# wsbd_wide.net
KiCad netlist of a schematic drawn in EAGLE
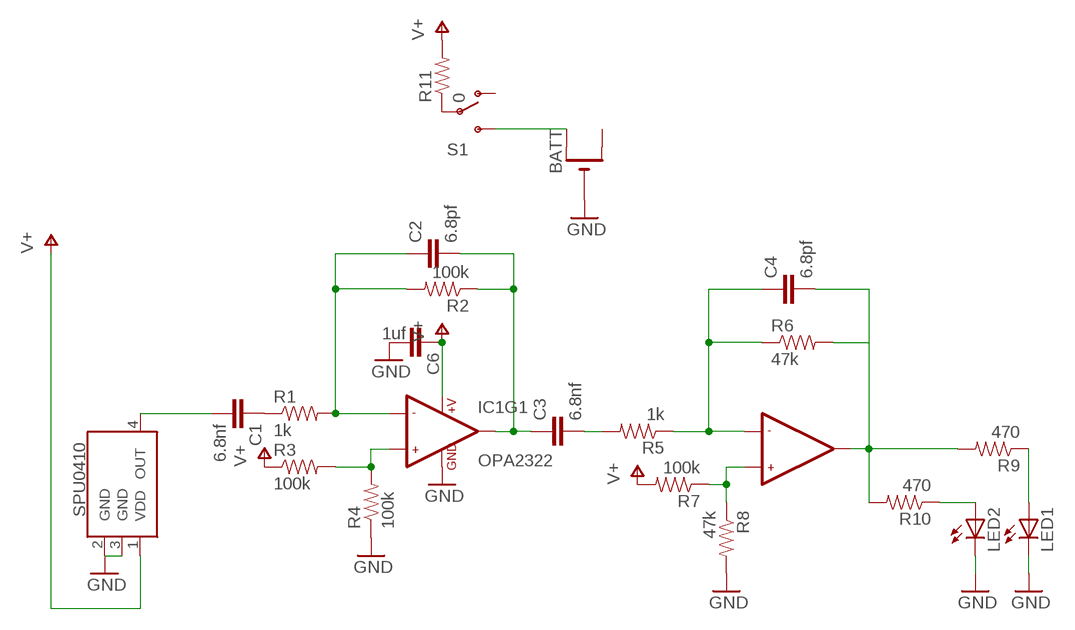
[diagram p0: schematic, sheet 1]

(export (version "E")
  (design (tool "Eeschema 10.0.6"))
  (components
    (comp (ref "BATT")
      (value "CR2032MPD1")
      (footprint "eagle-import:CR2032-THRU")
      (libsource (lib "eagle-import") (part "CR2032MPD1"))
    )
    (comp (ref "C1")
      (value "6.8nf")
      (footprint "eagle-import:0805")
      (libsource (lib "eagle-import") (part "CAP0805"))
    )
    (comp (ref "C2")
      (value "6.8pf")
      (footprint "eagle-import:0805")
      (libsource (lib "eagle-import") (part "CAP0805"))
    )
    (comp (ref "C3")
      (value "6.8nf")
      (footprint "eagle-import:0805")
      (libsource (lib "eagle-import") (part "CAP0805"))
    )
    (comp (ref "C4")
      (value "6.8pf")
      (footprint "eagle-import:0805")
      (libsource (lib "eagle-import") (part "CAP0805"))
    )
    (comp (ref "C6")
      (value "1uf")
      (footprint "eagle-import:0805")
      (libsource (lib "eagle-import") (part "CAP0805"))
    )
    (comp (ref "IC1")
      (value "OPA2322")
      (footprint "eagle-import:SO08")
      (libsource (lib "eagle-import") (part "LMV358SOIC"))
    )
    (comp (ref "LED1")
      (value "LEDCHIP-LED0805")
      (footprint "eagle-import:CHIP-LED0805")
      (libsource (lib "eagle-import") (part "LEDCHIP-LED0805"))
    )
    (comp (ref "LED2")
      (value "LEDCHIP-LED0805")
      (footprint "eagle-import:CHIP-LED0805")
      (libsource (lib "eagle-import") (part "LEDCHIP-LED0805"))
    )
    (comp (ref "R1")
      (value "1k")
      (footprint "eagle-import:0805")
      (libsource (lib "eagle-import") (part "RESISTOR0805-RES"))
    )
    (comp (ref "R2")
      (value "100k")
      (footprint "eagle-import:0805")
      (libsource (lib "eagle-import") (part "RESISTOR0805-RES"))
    )
    (comp (ref "R3")
      (value "100k")
      (footprint "eagle-import:0805")
      (libsource (lib "eagle-import") (part "RESISTOR0805-RES"))
    )
    (comp (ref "R4")
      (value "100k")
      (footprint "eagle-import:0805")
      (libsource (lib "eagle-import") (part "RESISTOR0805-RES"))
    )
    (comp (ref "R5")
      (value "1k")
      (footprint "eagle-import:0805")
      (libsource (lib "eagle-import") (part "RESISTOR0805-RES"))
    )
    (comp (ref "R6")
      (value "47k")
      (footprint "eagle-import:0805")
      (libsource (lib "eagle-import") (part "RESISTOR0805-RES"))
    )
    (comp (ref "R7")
      (value "100k")
      (footprint "eagle-import:0805")
      (libsource (lib "eagle-import") (part "RESISTOR0805-RES"))
    )
    (comp (ref "R8")
      (value "47k")
      (footprint "eagle-import:0805")
      (libsource (lib "eagle-import") (part "RESISTOR0805-RES"))
    )
    (comp (ref "R9")
      (value "470")
      (footprint "eagle-import:0805")
      (libsource (lib "eagle-import") (part "RESISTOR0805-RES"))
    )
    (comp (ref "R10")
      (value "470")
      (footprint "eagle-import:0805")
      (libsource (lib "eagle-import") (part "RESISTOR0805-RES"))
    )
    (comp (ref "R11")
      (value "0")
      (footprint "eagle-import:0805")
      (libsource (lib "eagle-import") (part "RESISTOR0805-RES"))
    )
    (comp (ref "S1")
      (value "SWITCH-SPDT-SMD-A")
      (footprint "eagle-import:SWITCH-SPST-SMD-A")
      (libsource (lib "eagle-import") (part "SWITCH-SPDT-SMD-A"))
    )
    (comp (ref "U$1")
      (value "SPU0410")
      (footprint "eagle-import:SPSERIES1")
      (libsource (lib "eagle-import") (part "SPU0410"))
    )
  )
  (nets
    (net (code "1") (name "GND") (class "Default")
      (node (ref "BATT") (pin "GND") (pinfunction "-_GND") (pintype "passive"))
      (node (ref "C6") (pin "2") (pinfunction "2_2") (pintype "passive"))
      (node (ref "IC1") (pin "4") (pinfunction "GND_4") (pintype "power_in"))
      (node (ref "LED1") (pin "C") (pinfunction "C_C") (pintype "passive"))
      (node (ref "LED2") (pin "C") (pinfunction "C_C") (pintype "passive"))
      (node (ref "R4") (pin "1") (pinfunction "1_1") (pintype "passive"))
      (node (ref "R8") (pin "2") (pinfunction "2_2") (pintype "passive"))
      (node (ref "U$1") (pin "2") (pinfunction "GND_2") (pintype "bidirectional"))
      (node (ref "U$1") (pin "3") (pinfunction "GND_3") (pintype "bidirectional"))
    )
    (net (code "2") (name "Net-(BATT-+)") (class "Default")
      (node (ref "BATT") (pin "+1") (pinfunction "+_+1") (pintype "passive"))
      (node (ref "S1") (pin "3") (pinfunction "S_3") (pintype "passive"))
    )
    (net (code "3") (name "Net-(C1-Pad1)") (class "Default")
      (node (ref "C1") (pin "1") (pinfunction "1_1") (pintype "passive"))
      (node (ref "R1") (pin "1") (pinfunction "1_1") (pintype "passive"))
    )
    (net (code "4") (name "Net-(C3-Pad2)") (class "Default")
      (node (ref "C3") (pin "2") (pinfunction "2_2") (pintype "passive"))
      (node (ref "R5") (pin "2") (pinfunction "2_2") (pintype "passive"))
    )
    (net (code "5") (name "Net-(IC1A-+IN1)") (class "Default")
      (node (ref "IC1") (pin "3") (pinfunction "+IN1_3") (pintype "input"))
      (node (ref "R3") (pin "2") (pinfunction "2_2") (pintype "passive"))
      (node (ref "R4") (pin "2") (pinfunction "2_2") (pintype "passive"))
    )
    (net (code "6") (name "Net-(IC1A--IN1)") (class "Default")
      (node (ref "C2") (pin "1") (pinfunction "1_1") (pintype "passive"))
      (node (ref "IC1") (pin "2") (pinfunction "-IN1_2") (pintype "input"))
      (node (ref "R1") (pin "2") (pinfunction "2_2") (pintype "passive"))
      (node (ref "R2") (pin "2") (pinfunction "2_2") (pintype "passive"))
    )
    (net (code "7") (name "Net-(IC1A-OUT1)") (class "Default")
      (node (ref "C2") (pin "2") (pinfunction "2_2") (pintype "passive"))
      (node (ref "C3") (pin "1") (pinfunction "1_1") (pintype "passive"))
      (node (ref "IC1") (pin "1") (pinfunction "OUT1_1") (pintype "output"))
      (node (ref "R2") (pin "1") (pinfunction "1_1") (pintype "passive"))
    )
    (net (code "8") (name "Net-(IC1B-+IN2)") (class "Default")
      (node (ref "IC1") (pin "5") (pinfunction "+IN2_5") (pintype "input"))
      (node (ref "R7") (pin "1") (pinfunction "1_1") (pintype "passive"))
      (node (ref "R8") (pin "1") (pinfunction "1_1") (pintype "passive"))
    )
    (net (code "9") (name "Net-(IC1B--IN2)") (class "Default")
      (node (ref "C4") (pin "1") (pinfunction "1_1") (pintype "passive"))
      (node (ref "IC1") (pin "6") (pinfunction "-IN2_6") (pintype "input"))
      (node (ref "R5") (pin "1") (pinfunction "1_1") (pintype "passive"))
      (node (ref "R6") (pin "1") (pinfunction "1_1") (pintype "passive"))
    )
    (net (code "10") (name "Net-(IC1B-OUT2)") (class "Default")
      (node (ref "C4") (pin "2") (pinfunction "2_2") (pintype "passive"))
      (node (ref "IC1") (pin "7") (pinfunction "OUT2_7") (pintype "output"))
      (node (ref "R10") (pin "2") (pinfunction "2_2") (pintype "passive"))
      (node (ref "R6") (pin "2") (pinfunction "2_2") (pintype "passive"))
      (node (ref "R9") (pin "2") (pinfunction "2_2") (pintype "passive"))
    )
    (net (code "11") (name "Net-(LED1-PadA)") (class "Default")
      (node (ref "LED1") (pin "A") (pinfunction "A_A") (pintype "passive"))
      (node (ref "R9") (pin "1") (pinfunction "1_1") (pintype "passive"))
    )
    (net (code "12") (name "Net-(LED2-PadA)") (class "Default")
      (node (ref "LED2") (pin "A") (pinfunction "A_A") (pintype "passive"))
      (node (ref "R10") (pin "1") (pinfunction "1_1") (pintype "passive"))
    )
    (net (code "13") (name "Net-(S1-P)") (class "Default")
      (node (ref "R11") (pin "1") (pinfunction "1_1") (pintype "passive"))
      (node (ref "S1") (pin "2") (pinfunction "P_2") (pintype "passive"))
    )
    (net (code "14") (name "Net-(U$1-OUT)") (class "Default")
      (node (ref "C1") (pin "2") (pinfunction "2_2") (pintype "passive"))
      (node (ref "U$1") (pin "4") (pinfunction "OUT_4") (pintype "bidirectional"))
    )
    (net (code "15") (name "V+") (class "Default")
      (node (ref "C6") (pin "1") (pinfunction "1_1") (pintype "passive"))
      (node (ref "IC1") (pin "8") (pinfunction "+V_8") (pintype "power_in"))
      (node (ref "R11") (pin "2") (pinfunction "2_2") (pintype "passive"))
      (node (ref "R3") (pin "1") (pinfunction "1_1") (pintype "passive"))
      (node (ref "R7") (pin "2") (pinfunction "2_2") (pintype "passive"))
      (node (ref "U$1") (pin "1") (pinfunction "VDD_1") (pintype "bidirectional"))
    )
    (net (code "16") (name "unconnected-(BATT-+1-Pad+2)") (class "Default")
      (node (ref "BATT") (pin "+2") (pinfunction "+1_+2") (pintype "passive"))
    )
    (net (code "17") (name "unconnected-(S1-O-Pad1)") (class "Default")
      (node (ref "S1") (pin "1") (pinfunction "O_1") (pintype "passive"))
    )
  )
)
